# 002_Battery.net
KiCad netlist of a schematic drawn in Altium Designer
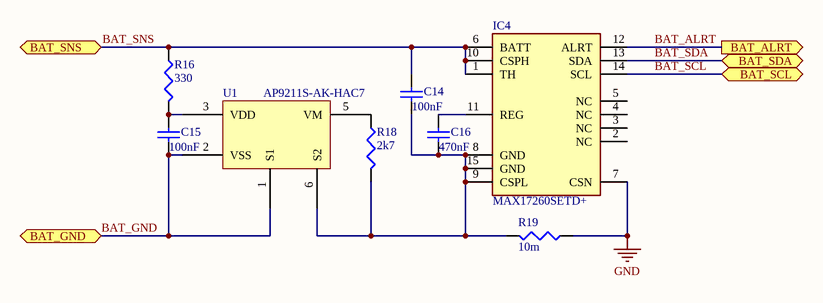
[diagram p0: [002] Battery.SchDoc]

(export (version "E")
  (design (tool "Eeschema 10.0.6"))
  (components
    (comp (ref "C14")
      (value "100nF")
      (footprint "1608[0603]")
      (description "Capacitor (Semiconductor SIM Model)")
      (fields (field (name "Comment") "Cap Semi") (field (name "PUBLISHER") "Altium Limited"))
      (libsource (lib "Miscellaneous Devices") (part "Cap Semi"))
    )
    (comp (ref "C15")
      (value "100nF")
      (footprint "1608[0603]")
      (description "Capacitor (Semiconductor SIM Model)")
      (fields (field (name "Comment") "Cap Semi") (field (name "PUBLISHER") "Altium Limited"))
      (libsource (lib "Miscellaneous Devices") (part "Cap Semi"))
    )
    (comp (ref "C16")
      (value "470nF")
      (footprint "1608[0603]")
      (description "Capacitor (Semiconductor SIM Model)")
      (fields (field (name "Comment") "Cap Semi") (field (name "PUBLISHER") "Altium Limited"))
      (libsource (lib "Miscellaneous Devices") (part "Cap Semi"))
    )
    (comp (ref "IC4")
      (value "MAX17260SETD+")
      (footprint "SamacSys:SON40P300X300X80-15N")
      (description "Integrated Circuit")
      (fields (field (name "MOUSER2 PART NUMBER") "700-MAX17260SETD+"))
      (libsource (lib "SamacSys") (part "MAX17260SETD+"))
    )
    (comp (ref "R16")
      (value "330")
      (footprint "J1-0603")
      (description "Resistor")
      (fields (field (name "Comment") "Res3") (field (name "PUBLISHER") "Altium Limited"))
      (libsource (lib "Miscellaneous Devices") (part "Res3"))
    )
    (comp (ref "R18")
      (value "2k7")
      (footprint "J1-0603")
      (description "Resistor")
      (fields (field (name "Comment") "Res3") (field (name "PUBLISHER") "Altium Limited"))
      (libsource (lib "Miscellaneous Devices") (part "Res3"))
    )
    (comp (ref "R19")
      (value "10m")
      (footprint "RESC3216X80N")
      (description "Resistor")
      (fields (field (name "Comment") "Res3") (field (name "PUBLISHER") "Altium Limited"))
      (libsource (lib "Miscellaneous Devices") (part "Res3"))
    )
    (comp (ref "U1")
      (value "AP9211S-AK-HAC7")
      (footprint "U-DFN2030-6")
      (description "SINGLE CHIP SOLUTION FOR 1-CELL Li+ BATTERY PACK")
      (libsource (lib "6DOF IMU_ver1") (part "AP9211"))
    )
  )
  (nets
    (net (code "1") (name "/BAT_ALRT") (class "Default")
      (node (ref "IC4") (pin "12") (pinfunction "ALRT_12") (pintype "passive"))
    )
    (net (code "2") (name "/BAT_GND") (class "Default")
      (node (ref "C15") (pin "1") (pinfunction "1_1") (pintype "passive"))
      (node (ref "U1") (pin "1") (pinfunction "S1_1") (pintype "passive"))
      (node (ref "U1") (pin "2") (pinfunction "VSS_2") (pintype "passive"))
    )
    (net (code "3") (name "/BAT_SCL") (class "Default")
      (node (ref "IC4") (pin "14") (pinfunction "SCL_14") (pintype "passive"))
    )
    (net (code "4") (name "/BAT_SDA") (class "Default")
      (node (ref "IC4") (pin "13") (pinfunction "SDA_13") (pintype "passive"))
    )
    (net (code "5") (name "/BAT_SNS") (class "Default")
      (node (ref "C14") (pin "2") (pinfunction "2_2") (pintype "passive"))
      (node (ref "IC4") (pin "1") (pinfunction "TH_1") (pintype "passive"))
      (node (ref "IC4") (pin "10") (pinfunction "CSPH_10") (pintype "passive"))
      (node (ref "IC4") (pin "6") (pinfunction "BATT_6") (pintype "passive"))
      (node (ref "R16") (pin "1") (pinfunction "1_1") (pintype "passive"))
    )
    (net (code "6") (name "GND") (class "Default")
      (node (ref "IC4") (pin "7") (pinfunction "CSN_7") (pintype "passive"))
      (node (ref "R19") (pin "1") (pinfunction "1_1") (pintype "passive"))
    )
    (net (code "7") (name "Net-(IC4-CSPL)") (class "Default")
      (node (ref "C14") (pin "1") (pinfunction "1_1") (pintype "passive"))
      (node (ref "C16") (pin "1") (pinfunction "1_1") (pintype "passive"))
      (node (ref "IC4") (pin "15") (pinfunction "GND_15") (pintype "passive"))
      (node (ref "IC4") (pin "8") (pinfunction "GND_8") (pintype "passive"))
      (node (ref "IC4") (pin "9") (pinfunction "CSPL_9") (pintype "passive"))
      (node (ref "R18") (pin "2") (pinfunction "2_2") (pintype "passive"))
      (node (ref "R19") (pin "2") (pinfunction "2_2") (pintype "passive"))
      (node (ref "U1") (pin "6") (pinfunction "S2_6") (pintype "passive"))
    )
    (net (code "8") (name "Net-(IC4-REG)") (class "Default")
      (node (ref "C16") (pin "2") (pinfunction "2_2") (pintype "passive"))
      (node (ref "IC4") (pin "11") (pinfunction "REG_11") (pintype "passive"))
    )
    (net (code "9") (name "Net-(U1-VDD)") (class "Default")
      (node (ref "C15") (pin "2") (pinfunction "2_2") (pintype "passive"))
      (node (ref "R16") (pin "2") (pinfunction "2_2") (pintype "passive"))
      (node (ref "U1") (pin "3") (pinfunction "VDD_3") (pintype "passive"))
    )
    (net (code "10") (name "Net-(U1-VM)") (class "Default")
      (node (ref "R18") (pin "1") (pinfunction "1_1") (pintype "passive"))
      (node (ref "U1") (pin "5") (pinfunction "VM_5") (pintype "passive"))
    )
    (net (code "11") (name "unconnected-(IC4-NC-Pad2)") (class "Default")
      (node (ref "IC4") (pin "2") (pinfunction "NC_2") (pintype "passive"))
    )
    (net (code "12") (name "unconnected-(IC4-NC-Pad3)") (class "Default")
      (node (ref "IC4") (pin "3") (pinfunction "NC_3") (pintype "passive"))
    )
    (net (code "13") (name "unconnected-(IC4-NC-Pad4)") (class "Default")
      (node (ref "IC4") (pin "4") (pinfunction "NC_4") (pintype "passive"))
    )
    (net (code "14") (name "unconnected-(IC4-NC-Pad5)") (class "Default")
      (node (ref "IC4") (pin "5") (pinfunction "NC_5") (pintype "passive"))
    )
  )
)
